# GRBL_Shield.net
KiCad netlist of a schematic drawn in EAGLE
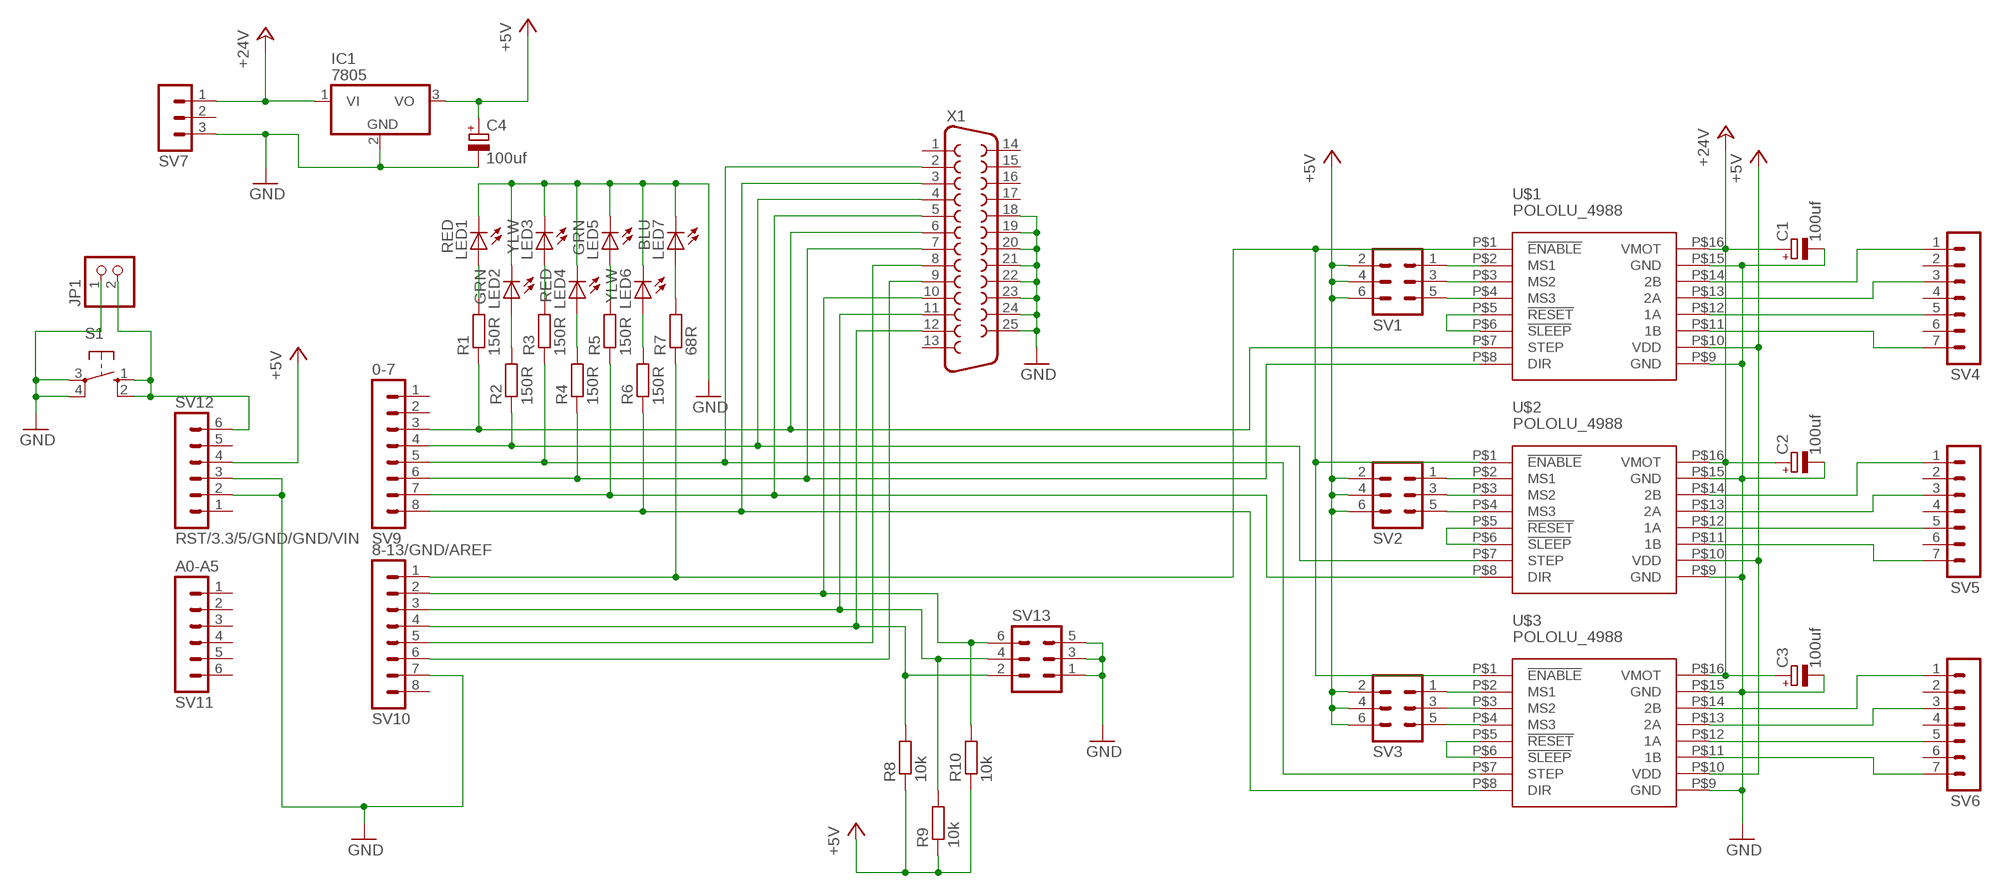
[diagram p0: schematic, sheet 1]

(export (version "E")
  (design (tool "Eeschema 10.0.6"))
  (components
    (comp (ref "C1")
      (value "100uf")
      (footprint "eagle-import:E2,5-7")
      (libsource (lib "eagle-import") (part "CPOL-EUE2.5-7"))
    )
    (comp (ref "C2")
      (value "100uf")
      (footprint "eagle-import:E2,5-7")
      (libsource (lib "eagle-import") (part "CPOL-EUE2.5-7"))
    )
    (comp (ref "C3")
      (value "100uf")
      (footprint "eagle-import:E2,5-7")
      (libsource (lib "eagle-import") (part "CPOL-EUE2.5-7"))
    )
    (comp (ref "C4")
      (value "100uf")
      (footprint "eagle-import:E2,5-7")
      (libsource (lib "eagle-import") (part "CPOL-EUE2.5-7"))
    )
    (comp (ref "IC1")
      (value "7805")
      (footprint "eagle-import:TO220V")
      (libsource (lib "eagle-import") (part "78TV6"))
    )
    (comp (ref "JP1")
      (value "PINHD-1X2")
      (footprint "eagle-import:1X02")
      (libsource (lib "eagle-import") (part "PINHD-1X2"))
    )
    (comp (ref "LED1")
      (value "RED")
      (footprint "eagle-import:LED5MM")
      (libsource (lib "eagle-import") (part "LED5MM"))
    )
    (comp (ref "LED2")
      (value "GRN")
      (footprint "eagle-import:LED5MM")
      (libsource (lib "eagle-import") (part "LED5MM"))
    )
    (comp (ref "LED3")
      (value "YLW")
      (footprint "eagle-import:LED5MM")
      (libsource (lib "eagle-import") (part "LED5MM"))
    )
    (comp (ref "LED4")
      (value "RED")
      (footprint "eagle-import:LED5MM")
      (libsource (lib "eagle-import") (part "LED5MM"))
    )
    (comp (ref "LED5")
      (value "GRN")
      (footprint "eagle-import:LED5MM")
      (libsource (lib "eagle-import") (part "LED5MM"))
    )
    (comp (ref "LED6")
      (value "YLW")
      (footprint "eagle-import:LED5MM")
      (libsource (lib "eagle-import") (part "LED5MM"))
    )
    (comp (ref "LED7")
      (value "BLU")
      (footprint "eagle-import:LED5MM")
      (libsource (lib "eagle-import") (part "LED5MM"))
    )
    (comp (ref "R1")
      (value "150R")
      (footprint "eagle-import:0207_2V")
      (libsource (lib "eagle-import") (part "R-EU_0207/2V"))
    )
    (comp (ref "R2")
      (value "150R")
      (footprint "eagle-import:0207_2V")
      (libsource (lib "eagle-import") (part "R-EU_0207/2V"))
    )
    (comp (ref "R3")
      (value "150R")
      (footprint "eagle-import:0207_2V")
      (libsource (lib "eagle-import") (part "R-EU_0207/2V"))
    )
    (comp (ref "R4")
      (value "150R")
      (footprint "eagle-import:0207_2V")
      (libsource (lib "eagle-import") (part "R-EU_0207/2V"))
    )
    (comp (ref "R5")
      (value "150R")
      (footprint "eagle-import:0207_2V")
      (libsource (lib "eagle-import") (part "R-EU_0207/2V"))
    )
    (comp (ref "R6")
      (value "150R")
      (footprint "eagle-import:0207_2V")
      (libsource (lib "eagle-import") (part "R-EU_0207/2V"))
    )
    (comp (ref "R7")
      (value "68R")
      (footprint "eagle-import:0207_2V")
      (libsource (lib "eagle-import") (part "R-EU_0207/2V"))
    )
    (comp (ref "R8")
      (value "10k")
      (footprint "eagle-import:0204_7")
      (libsource (lib "eagle-import") (part "R-EU_0204/7"))
    )
    (comp (ref "R9")
      (value "10k")
      (footprint "eagle-import:0204_7")
      (libsource (lib "eagle-import") (part "R-EU_0204/7"))
    )
    (comp (ref "R10")
      (value "10k")
      (footprint "eagle-import:0204_7")
      (libsource (lib "eagle-import") (part "R-EU_0204/7"))
    )
    (comp (ref "S1")
      (value "10-XX")
      (footprint "eagle-import:B3F-10XX")
      (fields (field (name "MPN") "B3F-1000"))
      (libsource (lib "eagle-import") (part "10-XX"))
    )
    (comp (ref "SV1")
      (value "MA03-2")
      (footprint "eagle-import:MA03-2")
      (libsource (lib "eagle-import") (part "MA03-2"))
    )
    (comp (ref "SV2")
      (value "MA03-2")
      (footprint "eagle-import:MA03-2")
      (libsource (lib "eagle-import") (part "MA03-2"))
    )
    (comp (ref "SV3")
      (value "MA03-2")
      (footprint "eagle-import:MA03-2")
      (libsource (lib "eagle-import") (part "MA03-2"))
    )
    (comp (ref "SV4")
      (value "MA07-1")
      (footprint "eagle-import:MA07-1")
      (libsource (lib "eagle-import") (part "MA07-1"))
    )
    (comp (ref "SV5")
      (value "MA07-1")
      (footprint "eagle-import:MA07-1")
      (libsource (lib "eagle-import") (part "MA07-1"))
    )
    (comp (ref "SV6")
      (value "MA07-1")
      (footprint "eagle-import:MA07-1")
      (libsource (lib "eagle-import") (part "MA07-1"))
    )
    (comp (ref "SV7")
      (value "MA03-1")
      (footprint "eagle-import:MA03-1")
      (libsource (lib "eagle-import") (part "MA03-1"))
    )
    (comp (ref "SV9")
      (value "0-7")
      (footprint "eagle-import:MA08-1")
      (libsource (lib "eagle-import") (part "MA08-1"))
    )
    (comp (ref "SV10")
      (value "8-13/GND/AREF")
      (footprint "eagle-import:MA08-1")
      (libsource (lib "eagle-import") (part "MA08-1"))
    )
    (comp (ref "SV11")
      (value "A0-A5")
      (footprint "eagle-import:MA06-1")
      (libsource (lib "eagle-import") (part "MA06-1"))
    )
    (comp (ref "SV12")
      (value "RST/3.3/5/GND/GND/VIN")
      (footprint "eagle-import:MA06-1")
      (libsource (lib "eagle-import") (part "MA06-1"))
    )
    (comp (ref "SV13")
      (value "MA03-2")
      (footprint "eagle-import:MA03-2")
      (libsource (lib "eagle-import") (part "MA03-2"))
    )
    (comp (ref "U$1")
      (value "POLOLU_4988")
      (footprint "eagle-import:POLOLU_4988")
      (libsource (lib "eagle-import") (part "POLOLU_4988"))
    )
    (comp (ref "U$2")
      (value "POLOLU_4988")
      (footprint "eagle-import:POLOLU_4988")
      (libsource (lib "eagle-import") (part "POLOLU_4988"))
    )
    (comp (ref "U$3")
      (value "POLOLU_4988")
      (footprint "eagle-import:POLOLU_4988")
      (libsource (lib "eagle-import") (part "POLOLU_4988"))
    )
    (comp (ref "X1")
      (value "F25H")
      (footprint "eagle-import:F25H")
      (libsource (lib "eagle-import") (part "F25H"))
    )
  )
  (nets
    (net (code "1") (name "+5V") (class "Default")
      (node (ref "C4") (pin "+") (pinfunction "+_+") (pintype "passive"))
      (node (ref "IC1") (pin "3") (pinfunction "VO_3") (pintype "passive"))
      (node (ref "R10") (pin "1") (pinfunction "1_1") (pintype "passive"))
      (node (ref "R8") (pin "1") (pinfunction "1_1") (pintype "passive"))
      (node (ref "R9") (pin "1") (pinfunction "1_1") (pintype "passive"))
      (node (ref "SV1") (pin "2") (pinfunction "2_2") (pintype "passive"))
      (node (ref "SV1") (pin "4") (pinfunction "4_4") (pintype "passive"))
      (node (ref "SV1") (pin "6") (pinfunction "6_6") (pintype "passive"))
      (node (ref "SV12") (pin "4") (pinfunction "4_4") (pintype "passive"))
      (node (ref "SV2") (pin "2") (pinfunction "2_2") (pintype "passive"))
      (node (ref "SV2") (pin "4") (pinfunction "4_4") (pintype "passive"))
      (node (ref "SV2") (pin "6") (pinfunction "6_6") (pintype "passive"))
      (node (ref "SV3") (pin "2") (pinfunction "2_2") (pintype "passive"))
      (node (ref "SV3") (pin "4") (pinfunction "4_4") (pintype "passive"))
      (node (ref "SV3") (pin "6") (pinfunction "6_6") (pintype "passive"))
      (node (ref "U$1") (pin "P$10") (pinfunction "VDD_P$10") (pintype "bidirectional"))
      (node (ref "U$2") (pin "P$10") (pinfunction "VDD_P$10") (pintype "bidirectional"))
      (node (ref "U$3") (pin "P$10") (pinfunction "VDD_P$10") (pintype "bidirectional"))
    )
    (net (code "2") (name "+24V") (class "Default")
      (node (ref "C1") (pin "+") (pinfunction "+_+") (pintype "passive"))
      (node (ref "C2") (pin "+") (pinfunction "+_+") (pintype "passive"))
      (node (ref "C3") (pin "+") (pinfunction "+_+") (pintype "passive"))
      (node (ref "IC1") (pin "1") (pinfunction "VI_1") (pintype "input"))
      (node (ref "SV7") (pin "1") (pinfunction "1_1") (pintype "passive"))
      (node (ref "U$1") (pin "P$16") (pinfunction "VMOT_P$16") (pintype "bidirectional"))
      (node (ref "U$2") (pin "P$16") (pinfunction "VMOT_P$16") (pintype "bidirectional"))
      (node (ref "U$3") (pin "P$16") (pinfunction "VMOT_P$16") (pintype "bidirectional"))
    )
    (net (code "3") (name "GND") (class "Default")
      (node (ref "C1") (pin "-") (pinfunction "-_-") (pintype "passive"))
      (node (ref "C2") (pin "-") (pinfunction "-_-") (pintype "passive"))
      (node (ref "C3") (pin "-") (pinfunction "-_-") (pintype "passive"))
      (node (ref "C4") (pin "-") (pinfunction "-_-") (pintype "passive"))
      (node (ref "IC1") (pin "2") (pinfunction "GND_2") (pintype "passive"))
      (node (ref "JP1") (pin "1") (pinfunction "1_1") (pintype "passive"))
      (node (ref "LED1") (pin "K") (pinfunction "C_K") (pintype "passive"))
      (node (ref "LED2") (pin "K") (pinfunction "C_K") (pintype "passive"))
      (node (ref "LED3") (pin "K") (pinfunction "C_K") (pintype "passive"))
      (node (ref "LED4") (pin "K") (pinfunction "C_K") (pintype "passive"))
      (node (ref "LED5") (pin "K") (pinfunction "C_K") (pintype "passive"))
      (node (ref "LED6") (pin "K") (pinfunction "C_K") (pintype "passive"))
      (node (ref "LED7") (pin "K") (pinfunction "C_K") (pintype "passive"))
      (node (ref "S1") (pin "3") (pinfunction "P_3") (pintype "passive"))
      (node (ref "S1") (pin "4") (pinfunction "P1_4") (pintype "passive"))
      (node (ref "SV10") (pin "7") (pinfunction "7_7") (pintype "passive"))
      (node (ref "SV12") (pin "2") (pinfunction "2_2") (pintype "passive"))
      (node (ref "SV12") (pin "3") (pinfunction "3_3") (pintype "passive"))
      (node (ref "SV13") (pin "1") (pinfunction "1_1") (pintype "passive"))
      (node (ref "SV13") (pin "3") (pinfunction "3_3") (pintype "passive"))
      (node (ref "SV13") (pin "5") (pinfunction "5_5") (pintype "passive"))
      (node (ref "SV7") (pin "3") (pinfunction "3_3") (pintype "passive"))
      (node (ref "U$1") (pin "P$15") (pinfunction "GND_P$15") (pintype "bidirectional"))
      (node (ref "U$1") (pin "P$9") (pinfunction "GND_P$9") (pintype "bidirectional"))
      (node (ref "U$2") (pin "P$15") (pinfunction "GND_P$15") (pintype "bidirectional"))
      (node (ref "U$2") (pin "P$9") (pinfunction "GND_P$9") (pintype "bidirectional"))
      (node (ref "U$3") (pin "P$15") (pinfunction "GND_P$15") (pintype "bidirectional"))
      (node (ref "U$3") (pin "P$9") (pinfunction "GND_P$9") (pintype "bidirectional"))
      (node (ref "X1") (pin "18") (pinfunction "18_18") (pintype "passive"))
      (node (ref "X1") (pin "19") (pinfunction "19_19") (pintype "passive"))
      (node (ref "X1") (pin "20") (pinfunction "20_20") (pintype "passive"))
      (node (ref "X1") (pin "21") (pinfunction "21_21") (pintype "passive"))
      (node (ref "X1") (pin "22") (pinfunction "22_22") (pintype "passive"))
      (node (ref "X1") (pin "23") (pinfunction "23_23") (pintype "passive"))
      (node (ref "X1") (pin "24") (pinfunction "24_24") (pintype "passive"))
      (node (ref "X1") (pin "25") (pinfunction "25_25") (pintype "passive"))
    )
    (net (code "4") (name "Net-(LED1-PadA)") (class "Default")
      (node (ref "LED1") (pin "A") (pinfunction "A_A") (pintype "passive"))
      (node (ref "R1") (pin "2") (pinfunction "2_2") (pintype "passive"))
    )
    (net (code "5") (name "Net-(LED2-PadA)") (class "Default")
      (node (ref "LED2") (pin "A") (pinfunction "A_A") (pintype "passive"))
      (node (ref "R2") (pin "2") (pinfunction "2_2") (pintype "passive"))
    )
    (net (code "6") (name "Net-(LED3-PadA)") (class "Default")
      (node (ref "LED3") (pin "A") (pinfunction "A_A") (pintype "passive"))
      (node (ref "R3") (pin "2") (pinfunction "2_2") (pintype "passive"))
    )
    (net (code "7") (name "Net-(LED4-PadA)") (class "Default")
      (node (ref "LED4") (pin "A") (pinfunction "A_A") (pintype "passive"))
      (node (ref "R4") (pin "2") (pinfunction "2_2") (pintype "passive"))
    )
    (net (code "8") (name "Net-(LED5-PadA)") (class "Default")
      (node (ref "LED5") (pin "A") (pinfunction "A_A") (pintype "passive"))
      (node (ref "R5") (pin "2") (pinfunction "2_2") (pintype "passive"))
    )
    (net (code "9") (name "Net-(LED6-PadA)") (class "Default")
      (node (ref "LED6") (pin "A") (pinfunction "A_A") (pintype "passive"))
      (node (ref "R6") (pin "2") (pinfunction "2_2") (pintype "passive"))
    )
    (net (code "10") (name "Net-(LED7-PadA)") (class "Default")
      (node (ref "LED7") (pin "A") (pinfunction "A_A") (pintype "passive"))
      (node (ref "R7") (pin "2") (pinfunction "2_2") (pintype "passive"))
    )
    (net (code "11") (name "Net-(R8-Pad2)") (class "Default")
      (node (ref "R8") (pin "2") (pinfunction "2_2") (pintype "passive"))
      (node (ref "SV10") (pin "4") (pinfunction "4_4") (pintype "passive"))
      (node (ref "SV13") (pin "2") (pinfunction "2_2") (pintype "passive"))
      (node (ref "X1") (pin "12") (pinfunction "12_12") (pintype "passive"))
    )
    (net (code "12") (name "Net-(R9-Pad2)") (class "Default")
      (node (ref "R9") (pin "2") (pinfunction "2_2") (pintype "passive"))
      (node (ref "SV10") (pin "3") (pinfunction "3_3") (pintype "passive"))
      (node (ref "SV13") (pin "4") (pinfunction "4_4") (pintype "passive"))
      (node (ref "X1") (pin "11") (pinfunction "11_11") (pintype "passive"))
    )
    (net (code "13") (name "Net-(R10-Pad2)") (class "Default")
      (node (ref "R10") (pin "2") (pinfunction "2_2") (pintype "passive"))
      (node (ref "SV10") (pin "2") (pinfunction "2_2") (pintype "passive"))
      (node (ref "SV13") (pin "6") (pinfunction "6_6") (pintype "passive"))
      (node (ref "X1") (pin "10") (pinfunction "10_10") (pintype "passive"))
    )
    (net (code "14") (name "Net-(S1-S)") (class "Default")
      (node (ref "JP1") (pin "2") (pinfunction "2_2") (pintype "passive"))
      (node (ref "S1") (pin "1") (pinfunction "S_1") (pintype "passive"))
      (node (ref "S1") (pin "2") (pinfunction "S1_2") (pintype "passive"))
      (node (ref "SV12") (pin "6") (pinfunction "6_6") (pintype "passive"))
    )
    (net (code "15") (name "Net-(SV10-Pad5)") (class "Default")
      (node (ref "SV10") (pin "5") (pinfunction "5_5") (pintype "passive"))
      (node (ref "X1") (pin "8") (pinfunction "8_8") (pintype "passive"))
    )
    (net (code "16") (name "Net-(SV10-Pad6)") (class "Default")
      (node (ref "SV10") (pin "6") (pinfunction "6_6") (pintype "passive"))
      (node (ref "X1") (pin "9") (pinfunction "9_9") (pintype "passive"))
    )
    (net (code "17") (name "Net-(U$1-1A)") (class "Default")
      (node (ref "SV4") (pin "5") (pinfunction "5_5") (pintype "passive"))
      (node (ref "U$1") (pin "P$12") (pinfunction "1A_P$12") (pintype "bidirectional"))
    )
    (net (code "18") (name "Net-(U$1-1B)") (class "Default")
      (node (ref "SV4") (pin "7") (pinfunction "7_7") (pintype "passive"))
      (node (ref "U$1") (pin "P$11") (pinfunction "1B_P$11") (pintype "bidirectional"))
    )
    (net (code "19") (name "Net-(U$1-2A)") (class "Default")
      (node (ref "SV4") (pin "3") (pinfunction "3_3") (pintype "passive"))
      (node (ref "U$1") (pin "P$13") (pinfunction "2A_P$13") (pintype "bidirectional"))
    )
    (net (code "20") (name "Net-(U$1-2B)") (class "Default")
      (node (ref "SV4") (pin "1") (pinfunction "1_1") (pintype "passive"))
      (node (ref "U$1") (pin "P$14") (pinfunction "2B_P$14") (pintype "bidirectional"))
    )
    (net (code "21") (name "Net-(U$1-DIR)") (class "Default")
      (node (ref "R4") (pin "1") (pinfunction "1_1") (pintype "passive"))
      (node (ref "SV9") (pin "6") (pinfunction "6_6") (pintype "passive"))
      (node (ref "U$1") (pin "P$8") (pinfunction "DIR_P$8") (pintype "bidirectional"))
      (node (ref "X1") (pin "7") (pinfunction "7_7") (pintype "passive"))
    )
    (net (code "22") (name "Net-(U$1-MS1)") (class "Default")
      (node (ref "SV1") (pin "1") (pinfunction "1_1") (pintype "passive"))
      (node (ref "U$1") (pin "P$2") (pinfunction "MS1_P$2") (pintype "bidirectional"))
    )
    (net (code "23") (name "Net-(U$1-MS2)") (class "Default")
      (node (ref "SV1") (pin "3") (pinfunction "3_3") (pintype "passive"))
      (node (ref "U$1") (pin "P$3") (pinfunction "MS2_P$3") (pintype "bidirectional"))
    )
    (net (code "24") (name "Net-(U$1-MS3)") (class "Default")
      (node (ref "SV1") (pin "5") (pinfunction "5_5") (pintype "passive"))
      (node (ref "U$1") (pin "P$4") (pinfunction "MS3_P$4") (pintype "bidirectional"))
    )
    (net (code "25") (name "Net-(U$1-STEP)") (class "Default")
      (node (ref "R1") (pin "1") (pinfunction "1_1") (pintype "passive"))
      (node (ref "SV9") (pin "3") (pinfunction "3_3") (pintype "passive"))
      (node (ref "U$1") (pin "P$7") (pinfunction "STEP_P$7") (pintype "bidirectional"))
      (node (ref "X1") (pin "6") (pinfunction "6_6") (pintype "passive"))
    )
    (net (code "26") (name "Net-(U$1-~{ENABLE})") (class "Default")
      (node (ref "R7") (pin "1") (pinfunction "1_1") (pintype "passive"))
      (node (ref "SV10") (pin "1") (pinfunction "1_1") (pintype "passive"))
      (node (ref "U$1") (pin "P$1") (pinfunction "~{ENABLE}_P$1") (pintype "bidirectional"))
      (node (ref "U$2") (pin "P$1") (pinfunction "~{ENABLE}_P$1") (pintype "bidirectional"))
      (node (ref "U$3") (pin "P$1") (pinfunction "~{ENABLE}_P$1") (pintype "bidirectional"))
    )
    (net (code "27") (name "Net-(U$1-~{RESET})") (class "Default")
      (node (ref "U$1") (pin "P$5") (pinfunction "~{RESET}_P$5") (pintype "bidirectional"))
      (node (ref "U$1") (pin "P$6") (pinfunction "~{SLEEP}_P$6") (pintype "bidirectional"))
    )
    (net (code "28") (name "Net-(U$2-1A)") (class "Default")
      (node (ref "SV5") (pin "5") (pinfunction "5_5") (pintype "passive"))
      (node (ref "U$2") (pin "P$12") (pinfunction "1A_P$12") (pintype "bidirectional"))
    )
    (net (code "29") (name "Net-(U$2-1B)") (class "Default")
      (node (ref "SV5") (pin "7") (pinfunction "7_7") (pintype "passive"))
      (node (ref "U$2") (pin "P$11") (pinfunction "1B_P$11") (pintype "bidirectional"))
    )
    (net (code "30") (name "Net-(U$2-2A)") (class "Default")
      (node (ref "SV5") (pin "3") (pinfunction "3_3") (pintype "passive"))
      (node (ref "U$2") (pin "P$13") (pinfunction "2A_P$13") (pintype "bidirectional"))
    )
    (net (code "31") (name "Net-(U$2-2B)") (class "Default")
      (node (ref "SV5") (pin "1") (pinfunction "1_1") (pintype "passive"))
      (node (ref "U$2") (pin "P$14") (pinfunction "2B_P$14") (pintype "bidirectional"))
    )
    (net (code "32") (name "Net-(U$2-DIR)") (class "Default")
      (node (ref "R5") (pin "1") (pinfunction "1_1") (pintype "passive"))
      (node (ref "SV9") (pin "7") (pinfunction "7_7") (pintype "passive"))
      (node (ref "U$2") (pin "P$8") (pinfunction "DIR_P$8") (pintype "bidirectional"))
      (node (ref "X1") (pin "5") (pinfunction "5_5") (pintype "passive"))
    )
    (net (code "33") (name "Net-(U$2-MS1)") (class "Default")
      (node (ref "SV2") (pin "1") (pinfunction "1_1") (pintype "passive"))
      (node (ref "U$2") (pin "P$2") (pinfunction "MS1_P$2") (pintype "bidirectional"))
    )
    (net (code "34") (name "Net-(U$2-MS2)") (class "Default")
      (node (ref "SV2") (pin "3") (pinfunction "3_3") (pintype "passive"))
      (node (ref "U$2") (pin "P$3") (pinfunction "MS2_P$3") (pintype "bidirectional"))
    )
    (net (code "35") (name "Net-(U$2-MS3)") (class "Default")
      (node (ref "SV2") (pin "5") (pinfunction "5_5") (pintype "passive"))
      (node (ref "U$2") (pin "P$4") (pinfunction "MS3_P$4") (pintype "bidirectional"))
    )
    (net (code "36") (name "Net-(U$2-STEP)") (class "Default")
      (node (ref "R2") (pin "1") (pinfunction "1_1") (pintype "passive"))
      (node (ref "SV9") (pin "4") (pinfunction "4_4") (pintype "passive"))
      (node (ref "U$2") (pin "P$7") (pinfunction "STEP_P$7") (pintype "bidirectional"))
      (node (ref "X1") (pin "4") (pinfunction "4_4") (pintype "passive"))
    )
    (net (code "37") (name "Net-(U$2-~{RESET})") (class "Default")
      (node (ref "U$2") (pin "P$5") (pinfunction "~{RESET}_P$5") (pintype "bidirectional"))
      (node (ref "U$2") (pin "P$6") (pinfunction "~{SLEEP}_P$6") (pintype "bidirectional"))
    )
    (net (code "38") (name "Net-(U$3-1A)") (class "Default")
      (node (ref "SV6") (pin "5") (pinfunction "5_5") (pintype "passive"))
      (node (ref "U$3") (pin "P$12") (pinfunction "1A_P$12") (pintype "bidirectional"))
    )
    (net (code "39") (name "Net-(U$3-1B)") (class "Default")
      (node (ref "SV6") (pin "7") (pinfunction "7_7") (pintype "passive"))
      (node (ref "U$3") (pin "P$11") (pinfunction "1B_P$11") (pintype "bidirectional"))
    )
    (net (code "40") (name "Net-(U$3-2A)") (class "Default")
      (node (ref "SV6") (pin "3") (pinfunction "3_3") (pintype "passive"))
      (node (ref "U$3") (pin "P$13") (pinfunction "2A_P$13") (pintype "bidirectional"))
    )
    (net (code "41") (name "Net-(U$3-2B)") (class "Default")
      (node (ref "SV6") (pin "1") (pinfunction "1_1") (pintype "passive"))
      (node (ref "U$3") (pin "P$14") (pinfunction "2B_P$14") (pintype "bidirectional"))
    )
    (net (code "42") (name "Net-(U$3-DIR)") (class "Default")
      (node (ref "R6") (pin "1") (pinfunction "1_1") (pintype "passive"))
      (node (ref "SV9") (pin "8") (pinfunction "8_8") (pintype "passive"))
      (node (ref "U$3") (pin "P$8") (pinfunction "DIR_P$8") (pintype "bidirectional"))
      (node (ref "X1") (pin "3") (pinfunction "3_3") (pintype "passive"))
    )
    (net (code "43") (name "Net-(U$3-MS1)") (class "Default")
      (node (ref "SV3") (pin "1") (pinfunction "1_1") (pintype "passive"))
      (node (ref "U$3") (pin "P$2") (pinfunction "MS1_P$2") (pintype "bidirectional"))
    )
    (net (code "44") (name "Net-(U$3-MS2)") (class "Default")
      (node (ref "SV3") (pin "3") (pinfunction "3_3") (pintype "passive"))
      (node (ref "U$3") (pin "P$3") (pinfunction "MS2_P$3") (pintype "bidirectional"))
    )
    (net (code "45") (name "Net-(U$3-MS3)") (class "Default")
      (node (ref "SV3") (pin "5") (pinfunction "5_5") (pintype "passive"))
      (node (ref "U$3") (pin "P$4") (pinfunction "MS3_P$4") (pintype "bidirectional"))
    )
    (net (code "46") (name "Net-(U$3-STEP)") (class "Default")
      (node (ref "R3") (pin "1") (pinfunction "1_1") (pintype "passive"))
      (node (ref "SV9") (pin "5") (pinfunction "5_5") (pintype "passive"))
      (node (ref "U$3") (pin "P$7") (pinfunction "STEP_P$7") (pintype "bidirectional"))
      (node (ref "X1") (pin "2") (pinfunction "2_2") (pintype "passive"))
    )
    (net (code "47") (name "Net-(U$3-~{RESET})") (class "Default")
      (node (ref "U$3") (pin "P$5") (pinfunction "~{RESET}_P$5") (pintype "bidirectional"))
      (node (ref "U$3") (pin "P$6") (pinfunction "~{SLEEP}_P$6") (pintype "bidirectional"))
    )
    (net (code "48") (name "unconnected-(SV4-Pad2)") (class "Default")
      (node (ref "SV4") (pin "2") (pinfunction "2_2") (pintype "passive"))
    )
    (net (code "49") (name "unconnected-(SV4-Pad4)") (class "Default")
      (node (ref "SV4") (pin "4") (pinfunction "4_4") (pintype "passive"))
    )
    (net (code "50") (name "unconnected-(SV4-Pad6)") (class "Default")
      (node (ref "SV4") (pin "6") (pinfunction "6_6") (pintype "passive"))
    )
    (net (code "51") (name "unconnected-(SV5-Pad2)") (class "Default")
      (node (ref "SV5") (pin "2") (pinfunction "2_2") (pintype "passive"))
    )
    (net (code "52") (name "unconnected-(SV5-Pad4)") (class "Default")
      (node (ref "SV5") (pin "4") (pinfunction "4_4") (pintype "passive"))
    )
    (net (code "53") (name "unconnected-(SV5-Pad6)") (class "Default")
      (node (ref "SV5") (pin "6") (pinfunction "6_6") (pintype "passive"))
    )
    (net (code "54") (name "unconnected-(SV6-Pad2)") (class "Default")
      (node (ref "SV6") (pin "2") (pinfunction "2_2") (pintype "passive"))
    )
    (net (code "55") (name "unconnected-(SV6-Pad4)") (class "Default")
      (node (ref "SV6") (pin "4") (pinfunction "4_4") (pintype "passive"))
    )
    (net (code "56") (name "unconnected-(SV6-Pad6)") (class "Default")
      (node (ref "SV6") (pin "6") (pinfunction "6_6") (pintype "passive"))
    )
    (net (code "57") (name "unconnected-(SV7-Pad2)") (class "Default")
      (node (ref "SV7") (pin "2") (pinfunction "2_2") (pintype "passive"))
    )
    (net (code "58") (name "unconnected-(SV9-Pad1)") (class "Default")
      (node (ref "SV9") (pin "1") (pinfunction "1_1") (pintype "passive"))
    )
    (net (code "59") (name "unconnected-(SV9-Pad2)") (class "Default")
      (node (ref "SV9") (pin "2") (pinfunction "2_2") (pintype "passive"))
    )
    (net (code "60") (name "unconnected-(SV10-Pad8)") (class "Default")
      (node (ref "SV10") (pin "8") (pinfunction "8_8") (pintype "passive"))
    )
    (net (code "61") (name "unconnected-(SV11-Pad1)") (class "Default")
      (node (ref "SV11") (pin "1") (pinfunction "1_1") (pintype "passive"))
    )
    (net (code "62") (name "unconnected-(SV11-Pad2)") (class "Default")
      (node (ref "SV11") (pin "2") (pinfunction "2_2") (pintype "passive"))
    )
    (net (code "63") (name "unconnected-(SV11-Pad3)") (class "Default")
      (node (ref "SV11") (pin "3") (pinfunction "3_3") (pintype "passive"))
    )
    (net (code "64") (name "unconnected-(SV11-Pad4)") (class "Default")
      (node (ref "SV11") (pin "4") (pinfunction "4_4") (pintype "passive"))
    )
    (net (code "65") (name "unconnected-(SV11-Pad5)") (class "Default")
      (node (ref "SV11") (pin "5") (pinfunction "5_5") (pintype "passive"))
    )
    (net (code "66") (name "unconnected-(SV11-Pad6)") (class "Default")
      (node (ref "SV11") (pin "6") (pinfunction "6_6") (pintype "passive"))
    )
    (net (code "67") (name "unconnected-(SV12-Pad1)") (class "Default")
      (node (ref "SV12") (pin "1") (pinfunction "1_1") (pintype "passive"))
    )
    (net (code "68") (name "unconnected-(SV12-Pad5)") (class "Default")
      (node (ref "SV12") (pin "5") (pinfunction "5_5") (pintype "passive"))
    )
    (net (code "69") (name "unconnected-(X1-Pad1)") (class "Default")
      (node (ref "X1") (pin "1") (pinfunction "1_1") (pintype "passive"))
    )
    (net (code "70") (name "unconnected-(X1-Pad13)") (class "Default")
      (node (ref "X1") (pin "13") (pinfunction "13_13") (pintype "passive"))
    )
    (net (code "71") (name "unconnected-(X1-Pad14)") (class "Default")
      (node (ref "X1") (pin "14") (pinfunction "14_14") (pintype "passive"))
    )
    (net (code "72") (name "unconnected-(X1-Pad15)") (class "Default")
      (node (ref "X1") (pin "15") (pinfunction "15_15") (pintype "passive"))
    )
    (net (code "73") (name "unconnected-(X1-Pad16)") (class "Default")
      (node (ref "X1") (pin "16") (pinfunction "16_16") (pintype "passive"))
    )
    (net (code "74") (name "unconnected-(X1-Pad17)") (class "Default")
      (node (ref "X1") (pin "17") (pinfunction "17_17") (pintype "passive"))
    )
  )
)
